# PCB_ESP.net
KiCad netlist of a schematic drawn in EAGLE
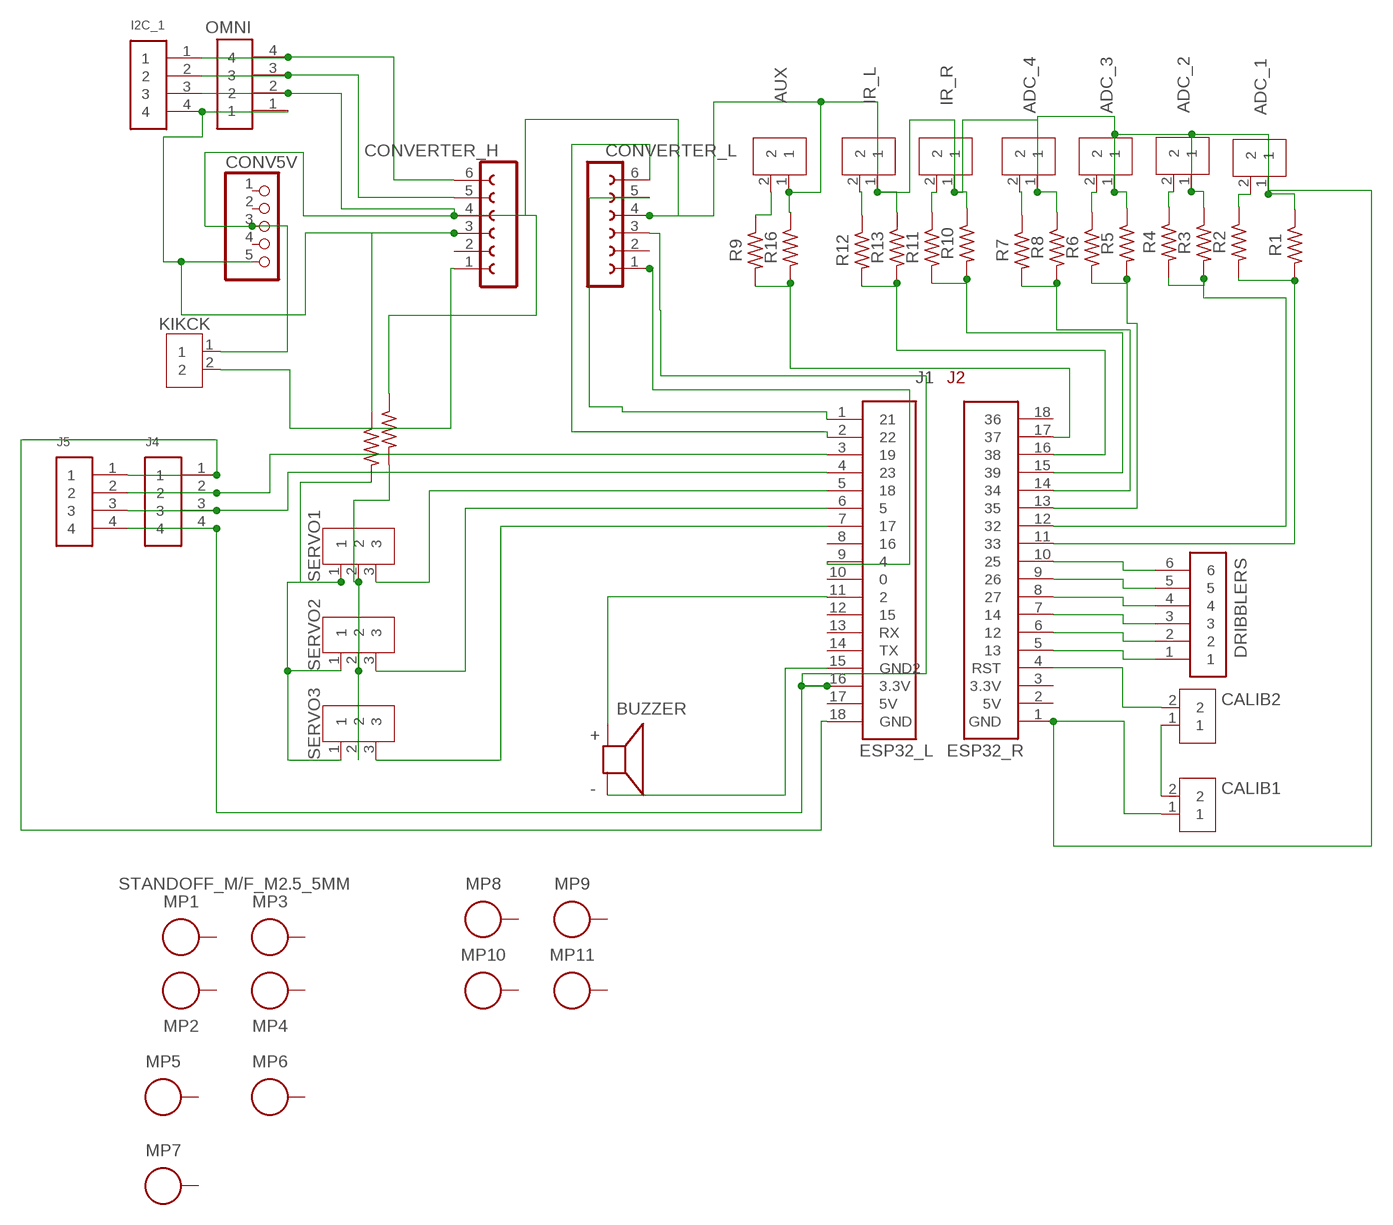
[diagram p0: schematic, sheet 1]

(export (version "E")
  (design (tool "Eeschema 10.0.6"))
  (components
    (comp (ref "ADC_1")
      (value "2828XX-2282834-2")
      (footprint "eagle-import:TERMBLK_254-2N")
      (libsource (lib "eagle-import") (part "2828XX-2282834-2"))
    )
    (comp (ref "ADC_2")
      (value "2828XX-2282834-2")
      (footprint "eagle-import:TERMBLK_254-2N")
      (libsource (lib "eagle-import") (part "2828XX-2282834-2"))
    )
    (comp (ref "ADC_3")
      (value "2828XX-2282834-2")
      (footprint "eagle-import:TERMBLK_254-2N")
      (libsource (lib "eagle-import") (part "2828XX-2282834-2"))
    )
    (comp (ref "ADC_4")
      (value "2828XX-2282834-2")
      (footprint "eagle-import:TERMBLK_254-2N")
      (libsource (lib "eagle-import") (part "2828XX-2282834-2"))
    )
    (comp (ref "AUX")
      (value "2828XX-2282834-2")
      (footprint "eagle-import:TERMBLK_254-2N")
      (libsource (lib "eagle-import") (part "2828XX-2282834-2"))
    )
    (comp (ref "BUZZER")
      (value "AT-1220-TT-9-R")
      (footprint "eagle-import:XDCR_AT-1220-TT-9-R")
      (fields (field (name "MANUFACTURER") "PUI Audio"))
      (libsource (lib "eagle-import") (part "AT-1220-TT-9-R"))
    )
    (comp (ref "CALIB1")
      (value "2828XX-2282834-2")
      (footprint "eagle-import:TERMBLK_254-2N")
      (libsource (lib "eagle-import") (part "2828XX-2282834-2"))
    )
    (comp (ref "CALIB2")
      (value "2828XX-2282834-2")
      (footprint "eagle-import:TERMBLK_254-2N")
      (libsource (lib "eagle-import") (part "2828XX-2282834-2"))
    )
    (comp (ref "CONV5V")
      (value "PINHD-1X55X2MM")
      (footprint "eagle-import:1_05X2MM")
      (libsource (lib "eagle-import") (part "PINHD-1X55X2MM"))
    )
    (comp (ref "CONVERTER_H")
      (value "FE06-1")
      (footprint "eagle-import:FE06")
      (libsource (lib "eagle-import") (part "FE06-1"))
    )
    (comp (ref "CONVERTER_L")
      (value "FE06-1")
      (footprint "eagle-import:FE06")
      (libsource (lib "eagle-import") (part "FE06-1"))
    )
    (comp (ref "DRIBBLERS")
      (value "61300611121")
      (footprint "eagle-import:61300611121")
      (fields
        (field (name "DIGI_KEY_PART_NUMBER") "732-5319-ND")
        (field (name "MANUFACTURER") "Wurth Electronics Inc.")
        (field (name "CREATED_BY") "PCBLayout.com")
      )
      (libsource (lib "eagle-import") (part "61300611121"))
    )
    (comp (ref "I2C_1")
      (value "61300411121")
      (footprint "eagle-import:61300411121")
      (fields
        (field (name "DIGI_KEY_PART_NUMBER") "732-5317-ND")
        (field (name "MANUFACTURER") "Wurth Electronics Inc.")
        (field (name "CREATED_BY") "PCBLayout.com")
      )
      (libsource (lib "eagle-import") (part "61300411121"))
    )
    (comp (ref "IR_L")
      (value "2828XX-2282834-2")
      (footprint "eagle-import:TERMBLK_254-2N")
      (libsource (lib "eagle-import") (part "2828XX-2282834-2"))
    )
    (comp (ref "IR_R")
      (value "2828XX-2282834-2")
      (footprint "eagle-import:TERMBLK_254-2N")
      (libsource (lib "eagle-import") (part "2828XX-2282834-2"))
    )
    (comp (ref "J1")
      (value "ESP32_L")
      (footprint "eagle-import:61301811121")
      (fields
        (field (name "DIGIKEY_PART_NUMBER") "732-5328-ND")
        (field (name "MANUFACTURER") "Wurth Electronics Inc.")
        (field (name "MPN") "61301811121")
        (field (name "CREATED_BY") "PCBLayout.com")
      )
      (libsource (lib "eagle-import") (part "ESP32_L"))
    )
    (comp (ref "J2")
      (value "ESP32_R")
      (footprint "eagle-import:61301811121")
      (fields
        (field (name "DIGIKEY_PART_NUMBER") "732-5328-ND")
        (field (name "MANUFACTURER") "Wurth Electronics Inc.")
        (field (name "MPN") "61301811121")
        (field (name "CREATED_BY") "PCBLayout.com")
      )
      (libsource (lib "eagle-import") (part "ESP32_R"))
    )
    (comp (ref "J4")
      (value "61300411121")
      (footprint "eagle-import:61300411121")
      (fields
        (field (name "DIGI_KEY_PART_NUMBER") "732-5317-ND")
        (field (name "MANUFACTURER") "Wurth Electronics Inc.")
        (field (name "CREATED_BY") "PCBLayout.com")
      )
      (libsource (lib "eagle-import") (part "61300411121"))
    )
    (comp (ref "J5")
      (value "61300411121")
      (footprint "eagle-import:61300411121")
      (fields
        (field (name "DIGI_KEY_PART_NUMBER") "732-5317-ND")
        (field (name "MANUFACTURER") "Wurth Electronics Inc.")
        (field (name "CREATED_BY") "PCBLayout.com")
      )
      (libsource (lib "eagle-import") (part "61300411121"))
    )
    (comp (ref "KIKCK")
      (value "2828XX-2282834-2")
      (footprint "eagle-import:TERMBLK_254-2N")
      (libsource (lib "eagle-import") (part "2828XX-2282834-2"))
    )
    (comp (ref "MP1")
      (value "STANDOFF_M/F_M2.5_5MM")
      (footprint "eagle-import:STANDOFF_HEX_MALE-FEMALE_500X500_M2.5X0.45_MTGP755H270")
      (libsource (lib "eagle-import") (part "STANDOFF_M/FM2.5_5MM_"))
    )
    (comp (ref "MP2")
      (value "STANDOFF_M/F_M2.5_5MM")
      (footprint "eagle-import:STANDOFF_HEX_MALE-FEMALE_500X500_M2.5X0.45_MTGP755H270")
      (libsource (lib "eagle-import") (part "STANDOFF_M/FM2.5_5MM_"))
    )
    (comp (ref "MP3")
      (value "STANDOFF_M/F_M2.5_5MM")
      (footprint "eagle-import:STANDOFF_HEX_MALE-FEMALE_500X500_M2.5X0.45_MTGP755H270")
      (libsource (lib "eagle-import") (part "STANDOFF_M/FM2.5_5MM_"))
    )
    (comp (ref "MP4")
      (value "STANDOFF_M/F_M2.5_5MM")
      (footprint "eagle-import:STANDOFF_HEX_MALE-FEMALE_500X500_M2.5X0.45_MTGP755H270")
      (libsource (lib "eagle-import") (part "STANDOFF_M/FM2.5_5MM_"))
    )
    (comp (ref "MP5")
      (value "STANDOFF_M/F_M2.5_5MM")
      (footprint "eagle-import:STANDOFF_HEX_MALE-FEMALE_500X500_M2.5X0.45_MTGP755H270")
      (libsource (lib "eagle-import") (part "STANDOFF_M/FM2.5_5MM_"))
    )
    (comp (ref "MP6")
      (value "STANDOFF_M/F_M2.5_5MM")
      (footprint "eagle-import:STANDOFF_HEX_MALE-FEMALE_500X500_M2.5X0.45_MTGP755H270")
      (libsource (lib "eagle-import") (part "STANDOFF_M/FM2.5_5MM_"))
    )
    (comp (ref "MP7")
      (value "STANDOFF_M/F_M2.5_5MM")
      (footprint "eagle-import:STANDOFF_HEX_MALE-FEMALE_500X500_M2.5X0.45_MTGP755H270")
      (libsource (lib "eagle-import") (part "STANDOFF_M/FM2.5_5MM_"))
    )
    (comp (ref "MP8")
      (value "STANDOFF_F/F_M2.5_5MM")
      (footprint "eagle-import:STANDOFF_HEX_FEMALE_500X500_M2.5X0.45_MTGP755H270")
      (libsource (lib "eagle-import") (part "STANDOFF_F/FM2.5_5MM_"))
    )
    (comp (ref "MP9")
      (value "STANDOFF_F/F_M2.5_5MM")
      (footprint "eagle-import:STANDOFF_HEX_FEMALE_500X500_M2.5X0.45_MTGP755H270")
      (libsource (lib "eagle-import") (part "STANDOFF_F/FM2.5_5MM_"))
    )
    (comp (ref "MP10")
      (value "STANDOFF_F/F_M2.5_5MM")
      (footprint "eagle-import:STANDOFF_HEX_FEMALE_500X500_M2.5X0.45_MTGP755H270")
      (libsource (lib "eagle-import") (part "STANDOFF_F/FM2.5_5MM_"))
    )
    (comp (ref "MP11")
      (value "STANDOFF_F/F_M2.5_5MM")
      (footprint "eagle-import:STANDOFF_HEX_FEMALE_500X500_M2.5X0.45_MTGP755H270")
      (libsource (lib "eagle-import") (part "STANDOFF_F/FM2.5_5MM_"))
    )
    (comp (ref "OMNI")
      (value "61300411121")
      (footprint "eagle-import:61300411121")
      (fields
        (field (name "DIGI_KEY_PART_NUMBER") "732-5317-ND")
        (field (name "MANUFACTURER") "Wurth Electronics Inc.")
        (field (name "CREATED_BY") "PCBLayout.com")
      )
      (libsource (lib "eagle-import") (part "61300411121"))
    )
    (comp (ref "R1")
      (value "R-US_AXIAL-7.2MM-PITCH")
      (footprint "eagle-import:RESAD724W46L381D178B")
      (libsource (lib "eagle-import") (part "R-USAXIAL-7.2MM-PITCH_"))
    )
    (comp (ref "R2")
      (value "R-US_AXIAL-7.2MM-PITCH")
      (footprint "eagle-import:RESAD724W46L381D178B")
      (libsource (lib "eagle-import") (part "R-USAXIAL-7.2MM-PITCH_"))
    )
    (comp (ref "R3")
      (value "R-US_AXIAL-7.2MM-PITCH")
      (footprint "eagle-import:RESAD724W46L381D178B")
      (libsource (lib "eagle-import") (part "R-USAXIAL-7.2MM-PITCH_"))
    )
    (comp (ref "R4")
      (value "R-US_AXIAL-7.2MM-PITCH")
      (footprint "eagle-import:RESAD724W46L381D178B")
      (libsource (lib "eagle-import") (part "R-USAXIAL-7.2MM-PITCH_"))
    )
    (comp (ref "R5")
      (value "R-US_AXIAL-7.2MM-PITCH")
      (footprint "eagle-import:RESAD724W46L381D178B")
      (libsource (lib "eagle-import") (part "R-USAXIAL-7.2MM-PITCH_"))
    )
    (comp (ref "R6")
      (value "R-US_AXIAL-7.2MM-PITCH")
      (footprint "eagle-import:RESAD724W46L381D178B")
      (libsource (lib "eagle-import") (part "R-USAXIAL-7.2MM-PITCH_"))
    )
    (comp (ref "R7")
      (value "R-US_AXIAL-7.2MM-PITCH")
      (footprint "eagle-import:RESAD724W46L381D178B")
      (libsource (lib "eagle-import") (part "R-USAXIAL-7.2MM-PITCH_"))
    )
    (comp (ref "R8")
      (value "R-US_AXIAL-7.2MM-PITCH")
      (footprint "eagle-import:RESAD724W46L381D178B")
      (libsource (lib "eagle-import") (part "R-USAXIAL-7.2MM-PITCH_"))
    )
    (comp (ref "R9")
      (value "R-US_AXIAL-7.2MM-PITCH")
      (footprint "eagle-import:RESAD724W46L381D178B")
      (libsource (lib "eagle-import") (part "R-USAXIAL-7.2MM-PITCH_"))
    )
    (comp (ref "R10")
      (value "R-US_AXIAL-7.2MM-PITCH")
      (footprint "eagle-import:RESAD724W46L381D178B")
      (libsource (lib "eagle-import") (part "R-USAXIAL-7.2MM-PITCH_"))
    )
    (comp (ref "R11")
      (value "R-US_AXIAL-7.2MM-PITCH")
      (footprint "eagle-import:RESAD724W46L381D178B")
      (libsource (lib "eagle-import") (part "R-USAXIAL-7.2MM-PITCH_"))
    )
    (comp (ref "R12")
      (value "R-US_AXIAL-7.2MM-PITCH")
      (footprint "eagle-import:RESAD724W46L381D178B")
      (libsource (lib "eagle-import") (part "R-USAXIAL-7.2MM-PITCH_"))
    )
    (comp (ref "R13")
      (value "R-US_AXIAL-7.2MM-PITCH")
      (footprint "eagle-import:RESAD724W46L381D178B")
      (libsource (lib "eagle-import") (part "R-USAXIAL-7.2MM-PITCH_"))
    )
    (comp (ref "R14")
      (value "R-US_AXIAL-7.2MM-PITCH")
      (footprint "eagle-import:RESAD724W46L381D178B")
      (libsource (lib "eagle-import") (part "R-USAXIAL-7.2MM-PITCH_"))
    )
    (comp (ref "R15")
      (value "R-US_AXIAL-7.2MM-PITCH")
      (footprint "eagle-import:RESAD724W46L381D178B")
      (libsource (lib "eagle-import") (part "R-USAXIAL-7.2MM-PITCH_"))
    )
    (comp (ref "R16")
      (value "R-US_AXIAL-7.2MM-PITCH")
      (footprint "eagle-import:RESAD724W46L381D178B")
      (libsource (lib "eagle-import") (part "R-USAXIAL-7.2MM-PITCH_"))
    )
    (comp (ref "SERVO1")
      (value "2828XX-3282834-3")
      (footprint "eagle-import:TERMBLK_254-3N")
      (fields (field (name "MANUFACTURER") "TE Connectivity") (field (name "MPN") "282834-3"))
      (libsource (lib "eagle-import") (part "2828XX-3282834-3"))
    )
    (comp (ref "SERVO2")
      (value "2828XX-3282834-3")
      (footprint "eagle-import:TERMBLK_254-3N")
      (fields (field (name "MANUFACTURER") "TE Connectivity") (field (name "MPN") "282834-3"))
      (libsource (lib "eagle-import") (part "2828XX-3282834-3"))
    )
    (comp (ref "SERVO3")
      (value "2828XX-3282834-3")
      (footprint "eagle-import:TERMBLK_254-3N")
      (fields (field (name "MANUFACTURER") "TE Connectivity") (field (name "MPN") "282834-3"))
      (libsource (lib "eagle-import") (part "2828XX-3282834-3"))
    )
  )
  (nets
    (net (code "1") (name "Net-(ADC_1-Pad2)") (class "Default")
      (node (ref "ADC_1") (pin "2") (pinfunction "2_2") (pintype "bidirectional"))
      (node (ref "R2") (pin "1") (pinfunction "1_1") (pintype "passive"))
    )
    (net (code "2") (name "Net-(ADC_2-Pad2)") (class "Default")
      (node (ref "ADC_2") (pin "2") (pinfunction "2_2") (pintype "bidirectional"))
      (node (ref "R4") (pin "1") (pinfunction "1_1") (pintype "passive"))
    )
    (net (code "3") (name "Net-(ADC_3-Pad2)") (class "Default")
      (node (ref "ADC_3") (pin "2") (pinfunction "2_2") (pintype "bidirectional"))
      (node (ref "R6") (pin "1") (pinfunction "1_1") (pintype "passive"))
    )
    (net (code "4") (name "Net-(ADC_4-Pad2)") (class "Default")
      (node (ref "ADC_4") (pin "2") (pinfunction "2_2") (pintype "bidirectional"))
      (node (ref "R7") (pin "1") (pinfunction "1_1") (pintype "passive"))
    )
    (net (code "5") (name "Net-(AUX-Pad2)") (class "Default")
      (node (ref "AUX") (pin "2") (pinfunction "2_2") (pintype "bidirectional"))
      (node (ref "R9") (pin "1") (pinfunction "1_1") (pintype "passive"))
    )
    (net (code "6") (name "Net-(CALIB1-Pad2)") (class "Default")
      (node (ref "CALIB1") (pin "2") (pinfunction "2_2") (pintype "bidirectional"))
      (node (ref "CALIB2") (pin "1") (pinfunction "1_1") (pintype "bidirectional"))
    )
    (net (code "7") (name "Net-(CONV5V-Pad5)") (class "Default")
      (node (ref "CONV5V") (pin "5") (pinfunction "5_5") (pintype "passive"))
      (node (ref "CONVERTER_H") (pin "3") (pinfunction "3_3") (pintype "passive"))
      (node (ref "I2C_1") (pin "4") (pinfunction "4_4") (pintype "passive"))
      (node (ref "OMNI") (pin "1") (pinfunction "1_1") (pintype "passive"))
      (node (ref "R14") (pin "1") (pinfunction "1_1") (pintype "passive"))
    )
    (net (code "8") (name "Net-(CONVERTER_H-Pad1)") (class "Default")
      (node (ref "CONVERTER_H") (pin "1") (pinfunction "1_1") (pintype "passive"))
      (node (ref "KIKCK") (pin "2") (pinfunction "2_2") (pintype "bidirectional"))
    )
    (net (code "9") (name "Net-(CONVERTER_H-Pad5)") (class "Default")
      (node (ref "CONVERTER_H") (pin "5") (pinfunction "5_5") (pintype "passive"))
      (node (ref "I2C_1") (pin "2") (pinfunction "2_2") (pintype "passive"))
      (node (ref "OMNI") (pin "3") (pinfunction "3_3") (pintype "passive"))
    )
    (net (code "10") (name "Net-(CONVERTER_H-Pad6)") (class "Default")
      (node (ref "CONVERTER_H") (pin "6") (pinfunction "6_6") (pintype "passive"))
      (node (ref "I2C_1") (pin "1") (pinfunction "1_1") (pintype "passive"))
      (node (ref "OMNI") (pin "4") (pinfunction "4_4") (pintype "passive"))
    )
    (net (code "11") (name "Net-(IR_L-Pad2)") (class "Default")
      (node (ref "IR_L") (pin "2") (pinfunction "2_2") (pintype "bidirectional"))
      (node (ref "R12") (pin "1") (pinfunction "1_1") (pintype "passive"))
    )
    (net (code "12") (name "Net-(IR_R-Pad2)") (class "Default")
      (node (ref "IR_R") (pin "2") (pinfunction "2_2") (pintype "bidirectional"))
      (node (ref "R11") (pin "1") (pinfunction "1_1") (pintype "passive"))
    )
    (net (code "13") (name "Net-(J1-2)") (class "Default")
      (node (ref "BUZZER") (pin "P") (pinfunction "P_P") (pintype "passive"))
      (node (ref "J1") (pin "11") (pinfunction "2_11") (pintype "passive"))
    )
    (net (code "14") (name "Net-(J1-3.3V)") (class "Default")
      (node (ref "CONVERTER_L") (pin "3") (pinfunction "3_3") (pintype "passive"))
      (node (ref "J1") (pin "16") (pinfunction "3.3V_16") (pintype "passive"))
      (node (ref "J4") (pin "4") (pinfunction "4_4") (pintype "passive"))
      (node (ref "J5") (pin "4") (pinfunction "4_4") (pintype "passive"))
    )
    (net (code "15") (name "Net-(J1-4)") (class "Default")
      (node (ref "CONVERTER_L") (pin "1") (pinfunction "1_1") (pintype "passive"))
      (node (ref "J1") (pin "9") (pinfunction "4_9") (pintype "passive"))
    )
    (net (code "16") (name "Net-(J1-5)") (class "Default")
      (node (ref "J1") (pin "6") (pinfunction "5_6") (pintype "passive"))
      (node (ref "SERVO2") (pin "3") (pinfunction "3_3") (pintype "bidirectional"))
    )
    (net (code "17") (name "Net-(J1-17)") (class "Default")
      (node (ref "J1") (pin "7") (pinfunction "17_7") (pintype "passive"))
      (node (ref "SERVO3") (pin "3") (pinfunction "3_3") (pintype "bidirectional"))
    )
    (net (code "18") (name "Net-(J1-18)") (class "Default")
      (node (ref "J1") (pin "5") (pinfunction "18_5") (pintype "passive"))
      (node (ref "SERVO1") (pin "3") (pinfunction "3_3") (pintype "bidirectional"))
    )
    (net (code "19") (name "Net-(J1-19)") (class "Default")
      (node (ref "J1") (pin "3") (pinfunction "19_3") (pintype "passive"))
      (node (ref "J4") (pin "2") (pinfunction "2_2") (pintype "passive"))
      (node (ref "J5") (pin "2") (pinfunction "2_2") (pintype "passive"))
    )
    (net (code "20") (name "Net-(J1-21)") (class "Default")
      (node (ref "CONVERTER_L") (pin "5") (pinfunction "5_5") (pintype "passive"))
      (node (ref "J1") (pin "1") (pinfunction "21_1") (pintype "passive"))
    )
    (net (code "21") (name "Net-(J1-22)") (class "Default")
      (node (ref "CONVERTER_L") (pin "6") (pinfunction "6_6") (pintype "passive"))
      (node (ref "J1") (pin "2") (pinfunction "22_2") (pintype "passive"))
    )
    (net (code "22") (name "Net-(J1-23)") (class "Default")
      (node (ref "J1") (pin "4") (pinfunction "23_4") (pintype "passive"))
      (node (ref "J4") (pin "3") (pinfunction "3_3") (pintype "passive"))
      (node (ref "J5") (pin "3") (pinfunction "3_3") (pintype "passive"))
    )
    (net (code "23") (name "Net-(J1-GND)") (class "Default")
      (node (ref "J1") (pin "18") (pinfunction "GND_18") (pintype "passive"))
      (node (ref "J4") (pin "1") (pinfunction "1_1") (pintype "passive"))
      (node (ref "J5") (pin "1") (pinfunction "1_1") (pintype "passive"))
    )
    (net (code "24") (name "Net-(J1-GND2)") (class "Default")
      (node (ref "BUZZER") (pin "N") (pinfunction "N_N") (pintype "passive"))
      (node (ref "J1") (pin "15") (pinfunction "GND2_15") (pintype "passive"))
    )
    (net (code "25") (name "Net-(J2-12)") (class "Default")
      (node (ref "DRIBBLERS") (pin "2") (pinfunction "2_2") (pintype "passive"))
      (node (ref "J2") (pin "6") (pinfunction "12_6") (pintype "passive"))
    )
    (net (code "26") (name "Net-(J2-13)") (class "Default")
      (node (ref "DRIBBLERS") (pin "1") (pinfunction "1_1") (pintype "passive"))
      (node (ref "J2") (pin "5") (pinfunction "13_5") (pintype "passive"))
    )
    (net (code "27") (name "Net-(J2-14)") (class "Default")
      (node (ref "DRIBBLERS") (pin "3") (pinfunction "3_3") (pintype "passive"))
      (node (ref "J2") (pin "7") (pinfunction "14_7") (pintype "passive"))
    )
    (net (code "28") (name "Net-(J2-25)") (class "Default")
      (node (ref "DRIBBLERS") (pin "6") (pinfunction "6_6") (pintype "passive"))
      (node (ref "J2") (pin "10") (pinfunction "25_10") (pintype "passive"))
    )
    (net (code "29") (name "Net-(J2-26)") (class "Default")
      (node (ref "DRIBBLERS") (pin "5") (pinfunction "5_5") (pintype "passive"))
      (node (ref "J2") (pin "9") (pinfunction "26_9") (pintype "passive"))
    )
    (net (code "30") (name "Net-(J2-27)") (class "Default")
      (node (ref "DRIBBLERS") (pin "4") (pinfunction "4_4") (pintype "passive"))
      (node (ref "J2") (pin "8") (pinfunction "27_8") (pintype "passive"))
    )
    (net (code "31") (name "Net-(J2-32)") (class "Default")
      (node (ref "J2") (pin "12") (pinfunction "32_12") (pintype "passive"))
      (node (ref "R3") (pin "2") (pinfunction "2_2") (pintype "passive"))
      (node (ref "R4") (pin "2") (pinfunction "2_2") (pintype "passive"))
    )
    (net (code "32") (name "Net-(J2-33)") (class "Default")
      (node (ref "J2") (pin "11") (pinfunction "33_11") (pintype "passive"))
      (node (ref "R1") (pin "2") (pinfunction "2_2") (pintype "passive"))
      (node (ref "R2") (pin "2") (pinfunction "2_2") (pintype "passive"))
    )
    (net (code "33") (name "Net-(J2-34)") (class "Default")
      (node (ref "J2") (pin "14") (pinfunction "34_14") (pintype "passive"))
      (node (ref "R7") (pin "2") (pinfunction "2_2") (pintype "passive"))
      (node (ref "R8") (pin "2") (pinfunction "2_2") (pintype "passive"))
    )
    (net (code "34") (name "Net-(J2-35)") (class "Default")
      (node (ref "J2") (pin "13") (pinfunction "35_13") (pintype "passive"))
      (node (ref "R5") (pin "2") (pinfunction "2_2") (pintype "passive"))
      (node (ref "R6") (pin "2") (pinfunction "2_2") (pintype "passive"))
    )
    (net (code "35") (name "Net-(J2-37)") (class "Default")
      (node (ref "J2") (pin "17") (pinfunction "37_17") (pintype "passive"))
      (node (ref "R16") (pin "2") (pinfunction "2_2") (pintype "passive"))
      (node (ref "R9") (pin "2") (pinfunction "2_2") (pintype "passive"))
    )
    (net (code "36") (name "Net-(J2-38)") (class "Default")
      (node (ref "J2") (pin "16") (pinfunction "38_16") (pintype "passive"))
      (node (ref "R12") (pin "2") (pinfunction "2_2") (pintype "passive"))
      (node (ref "R13") (pin "2") (pinfunction "2_2") (pintype "passive"))
    )
    (net (code "37") (name "Net-(J2-39)") (class "Default")
      (node (ref "J2") (pin "15") (pinfunction "39_15") (pintype "passive"))
      (node (ref "R10") (pin "2") (pinfunction "2_2") (pintype "passive"))
      (node (ref "R11") (pin "2") (pinfunction "2_2") (pintype "passive"))
    )
    (net (code "38") (name "Net-(J2-GND)") (class "Default")
      (node (ref "ADC_1") (pin "1") (pinfunction "1_1") (pintype "bidirectional"))
      (node (ref "ADC_2") (pin "1") (pinfunction "1_1") (pintype "bidirectional"))
      (node (ref "ADC_3") (pin "1") (pinfunction "1_1") (pintype "bidirectional"))
      (node (ref "ADC_4") (pin "1") (pinfunction "1_1") (pintype "bidirectional"))
      (node (ref "AUX") (pin "1") (pinfunction "1_1") (pintype "bidirectional"))
      (node (ref "CALIB1") (pin "1") (pinfunction "1_1") (pintype "bidirectional"))
      (node (ref "CONV5V") (pin "3") (pinfunction "3_3") (pintype "passive"))
      (node (ref "CONVERTER_H") (pin "4") (pinfunction "4_4") (pintype "passive"))
      (node (ref "CONVERTER_L") (pin "4") (pinfunction "4_4") (pintype "passive"))
      (node (ref "I2C_1") (pin "3") (pinfunction "3_3") (pintype "passive"))
      (node (ref "IR_L") (pin "1") (pinfunction "1_1") (pintype "bidirectional"))
      (node (ref "IR_R") (pin "1") (pinfunction "1_1") (pintype "bidirectional"))
      (node (ref "J2") (pin "1") (pinfunction "GND_1") (pintype "passive"))
      (node (ref "KIKCK") (pin "1") (pinfunction "1_1") (pintype "bidirectional"))
      (node (ref "OMNI") (pin "2") (pinfunction "2_2") (pintype "passive"))
      (node (ref "R1") (pin "1") (pinfunction "1_1") (pintype "passive"))
      (node (ref "R10") (pin "1") (pinfunction "1_1") (pintype "passive"))
      (node (ref "R13") (pin "1") (pinfunction "1_1") (pintype "passive"))
      (node (ref "R15") (pin "1") (pinfunction "1_1") (pintype "passive"))
      (node (ref "R16") (pin "1") (pinfunction "1_1") (pintype "passive"))
      (node (ref "R3") (pin "1") (pinfunction "1_1") (pintype "passive"))
      (node (ref "R5") (pin "1") (pinfunction "1_1") (pintype "passive"))
      (node (ref "R8") (pin "1") (pinfunction "1_1") (pintype "passive"))
    )
    (net (code "39") (name "Net-(J2-RST)") (class "Default")
      (node (ref "CALIB2") (pin "2") (pinfunction "2_2") (pintype "bidirectional"))
      (node (ref "J2") (pin "4") (pinfunction "RST_4") (pintype "passive"))
    )
    (net (code "40") (name "Net-(R14-Pad2)") (class "Default")
      (node (ref "R14") (pin "2") (pinfunction "2_2") (pintype "passive"))
      (node (ref "SERVO1") (pin "1") (pinfunction "1_1") (pintype "bidirectional"))
      (node (ref "SERVO2") (pin "1") (pinfunction "1_1") (pintype "bidirectional"))
      (node (ref "SERVO3") (pin "1") (pinfunction "1_1") (pintype "bidirectional"))
    )
    (net (code "41") (name "Net-(R15-Pad2)") (class "Default")
      (node (ref "R15") (pin "2") (pinfunction "2_2") (pintype "passive"))
      (node (ref "SERVO1") (pin "2") (pinfunction "2_2") (pintype "bidirectional"))
      (node (ref "SERVO2") (pin "2") (pinfunction "2_2") (pintype "bidirectional"))
      (node (ref "SERVO3") (pin "2") (pinfunction "2_2") (pintype "bidirectional"))
    )
    (net (code "42") (name "unconnected-(CONV5V-Pad1)") (class "Default")
      (node (ref "CONV5V") (pin "1") (pinfunction "1_1") (pintype "passive"))
    )
    (net (code "43") (name "unconnected-(CONV5V-Pad2)") (class "Default")
      (node (ref "CONV5V") (pin "2") (pinfunction "2_2") (pintype "passive"))
    )
    (net (code "44") (name "unconnected-(CONV5V-Pad4)") (class "Default")
      (node (ref "CONV5V") (pin "4") (pinfunction "4_4") (pintype "passive"))
    )
    (net (code "45") (name "unconnected-(CONVERTER_H-Pad2)") (class "Default")
      (node (ref "CONVERTER_H") (pin "2") (pinfunction "2_2") (pintype "passive"))
    )
    (net (code "46") (name "unconnected-(CONVERTER_L-Pad2)") (class "Default")
      (node (ref "CONVERTER_L") (pin "2") (pinfunction "2_2") (pintype "passive"))
    )
    (net (code "47") (name "unconnected-(J1-0-Pad10)") (class "Default")
      (node (ref "J1") (pin "10") (pinfunction "0_10") (pintype "passive"))
    )
    (net (code "48") (name "unconnected-(J1-5V-Pad17)") (class "Default")
      (node (ref "J1") (pin "17") (pinfunction "5V_17") (pintype "passive"))
    )
    (net (code "49") (name "unconnected-(J1-15-Pad12)") (class "Default")
      (node (ref "J1") (pin "12") (pinfunction "15_12") (pintype "passive"))
    )
    (net (code "50") (name "unconnected-(J1-16-Pad8)") (class "Default")
      (node (ref "J1") (pin "8") (pinfunction "16_8") (pintype "passive"))
    )
    (net (code "51") (name "unconnected-(J1-RX-Pad13)") (class "Default")
      (node (ref "J1") (pin "13") (pinfunction "RX_13") (pintype "passive"))
    )
    (net (code "52") (name "unconnected-(J1-TX-Pad14)") (class "Default")
      (node (ref "J1") (pin "14") (pinfunction "TX_14") (pintype "passive"))
    )
    (net (code "53") (name "unconnected-(J2-3.3V-Pad3)") (class "Default")
      (node (ref "J2") (pin "3") (pinfunction "3.3V_3") (pintype "passive"))
    )
    (net (code "54") (name "unconnected-(J2-5V-Pad2)") (class "Default")
      (node (ref "J2") (pin "2") (pinfunction "5V_2") (pintype "passive"))
    )
    (net (code "55") (name "unconnected-(J2-36-Pad18)") (class "Default")
      (node (ref "J2") (pin "18") (pinfunction "36_18") (pintype "passive"))
    )
    (net (code "56") (name "unconnected-(MP1-P$1-Pad1)") (class "Default")
      (node (ref "MP1") (pin "1") (pinfunction "P$1_1") (pintype "passive"))
    )
    (net (code "57") (name "unconnected-(MP2-P$1-Pad1)") (class "Default")
      (node (ref "MP2") (pin "1") (pinfunction "P$1_1") (pintype "passive"))
    )
    (net (code "58") (name "unconnected-(MP3-P$1-Pad1)") (class "Default")
      (node (ref "MP3") (pin "1") (pinfunction "P$1_1") (pintype "passive"))
    )
    (net (code "59") (name "unconnected-(MP4-P$1-Pad1)") (class "Default")
      (node (ref "MP4") (pin "1") (pinfunction "P$1_1") (pintype "passive"))
    )
    (net (code "60") (name "unconnected-(MP5-P$1-Pad1)") (class "Default")
      (node (ref "MP5") (pin "1") (pinfunction "P$1_1") (pintype "passive"))
    )
    (net (code "61") (name "unconnected-(MP6-P$1-Pad1)") (class "Default")
      (node (ref "MP6") (pin "1") (pinfunction "P$1_1") (pintype "passive"))
    )
    (net (code "62") (name "unconnected-(MP7-P$1-Pad1)") (class "Default")
      (node (ref "MP7") (pin "1") (pinfunction "P$1_1") (pintype "passive"))
    )
    (net (code "63") (name "unconnected-(MP8-P$1-Pad1)") (class "Default")
      (node (ref "MP8") (pin "1") (pinfunction "P$1_1") (pintype "passive"))
    )
    (net (code "64") (name "unconnected-(MP9-P$1-Pad1)") (class "Default")
      (node (ref "MP9") (pin "1") (pinfunction "P$1_1") (pintype "passive"))
    )
    (net (code "65") (name "unconnected-(MP10-P$1-Pad1)") (class "Default")
      (node (ref "MP10") (pin "1") (pinfunction "P$1_1") (pintype "passive"))
    )
    (net (code "66") (name "unconnected-(MP11-P$1-Pad1)") (class "Default")
      (node (ref "MP11") (pin "1") (pinfunction "P$1_1") (pintype "passive"))
    )
  )
)
